# KEYBOARD.net
KiCad netlist of a schematic drawn in Altium Designer
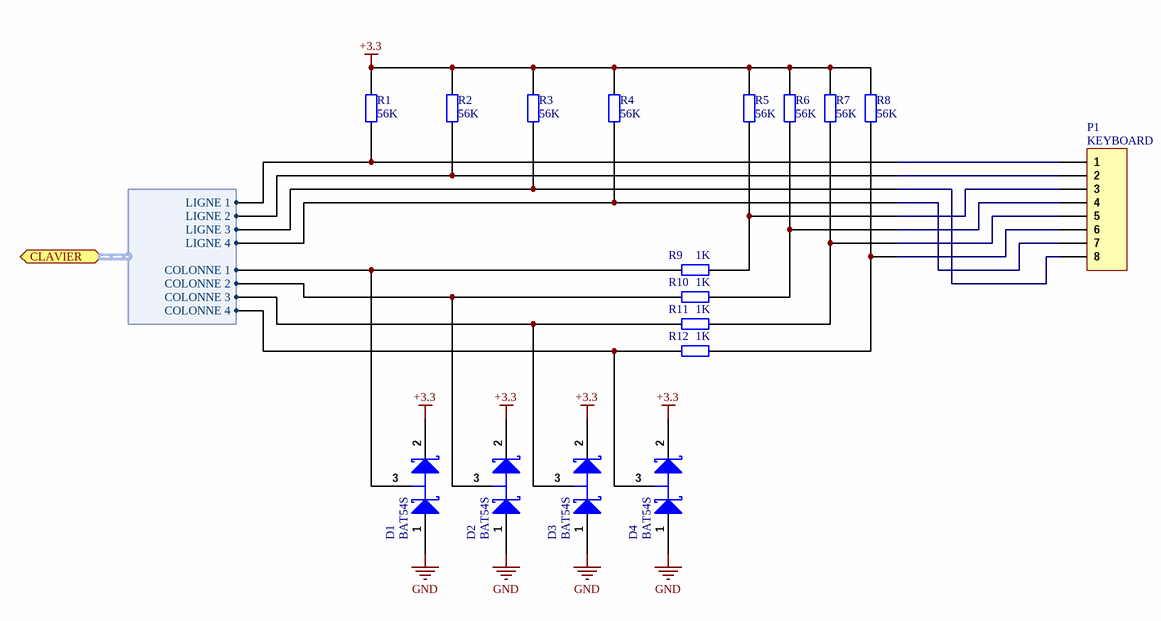
[diagram p0: KEYBOARD.SchDoc]

(export (version "E")
  (design (tool "Eeschema 10.0.6"))
  (components
    (comp (ref "D1")
      (value "BAT54S")
      (footprint "SOT-23")
      (description "Schottky Barrier Double Diode")
      (fields (field (name "MANUFACTURER") "MULTICOMP") (field (name "PUBLISHER") "Altium Limited"))
      (libsource (lib "Philips Discrete Diode - Schottky") (part "BAT54S"))
    )
    (comp (ref "D2")
      (value "BAT54S")
      (footprint "SOT-23")
      (description "Schottky Barrier Double Diode")
      (fields (field (name "MANUFACTURER") "MULTICOMP") (field (name "PUBLISHER") "Altium Limited"))
      (libsource (lib "Philips Discrete Diode - Schottky") (part "BAT54S"))
    )
    (comp (ref "D3")
      (value "BAT54S")
      (footprint "SOT-23")
      (description "Schottky Barrier Double Diode")
      (fields (field (name "MANUFACTURER") "MULTICOMP") (field (name "PUBLISHER") "Altium Limited"))
      (libsource (lib "Philips Discrete Diode - Schottky") (part "BAT54S"))
    )
    (comp (ref "D4")
      (value "BAT54S")
      (footprint "SOT-23")
      (description "Schottky Barrier Double Diode")
      (fields (field (name "MANUFACTURER") "MULTICOMP") (field (name "PUBLISHER") "Altium Limited"))
      (libsource (lib "Philips Discrete Diode - Schottky") (part "BAT54S"))
    )
    (comp (ref "P1")
      (value "KEYBOARD")
      (footprint "M20_1X8")
      (description "Header, 8-Pin")
      (fields
        (field (name "MANUFACTURER") "HARWIN")
        (field (name "MANUFACTURER PART NUMBER") "M20-8770842")
        (field (name "PUBLISHER") "Altium Limited")
      )
      (libsource (lib "Miscellaneous Connectors") (part "Header 8"))
    )
    (comp (ref "R1")
      (value "56K")
      (footprint "R0805")
      (description "Resistor")
      (fields
        (field (name "MANUFACTURER") "MULTICOMP")
        (field (name "MANUFACTURER PART NUMBER") "MC0.1W08051%56KFR")
      )
      (libsource (lib "BRA") (part "Resistor 0805 56K"))
    )
    (comp (ref "R2")
      (value "56K")
      (footprint "R0805")
      (description "Resistor")
      (fields
        (field (name "MANUFACTURER") "MULTICOMP")
        (field (name "MANUFACTURER PART NUMBER") "MC0.1W08051%56KFR")
      )
      (libsource (lib "BRA") (part "Resistor 0805 56K"))
    )
    (comp (ref "R3")
      (value "56K")
      (footprint "R0805")
      (description "Resistor")
      (fields
        (field (name "MANUFACTURER") "MULTICOMP")
        (field (name "MANUFACTURER PART NUMBER") "MC0.1W08051%56KFR")
      )
      (libsource (lib "BRA") (part "Resistor 0805 56K"))
    )
    (comp (ref "R4")
      (value "56K")
      (footprint "R0805")
      (description "Resistor")
      (fields
        (field (name "MANUFACTURER") "MULTICOMP")
        (field (name "MANUFACTURER PART NUMBER") "MC0.1W08051%56KFR")
      )
      (libsource (lib "BRA") (part "Resistor 0805 56K"))
    )
    (comp (ref "R5")
      (value "56K")
      (footprint "R0805")
      (description "Resistor")
      (fields
        (field (name "MANUFACTURER") "MULTICOMP")
        (field (name "MANUFACTURER PART NUMBER") "MC0.1W08051%56KFR")
      )
      (libsource (lib "BRA") (part "Resistor 0805 56K"))
    )
    (comp (ref "R6")
      (value "56K")
      (footprint "R0805")
      (description "Resistor")
      (fields
        (field (name "MANUFACTURER") "MULTICOMP")
        (field (name "MANUFACTURER PART NUMBER") "MC0.1W08051%56KFR")
      )
      (libsource (lib "BRA") (part "Resistor 0805 56K"))
    )
    (comp (ref "R7")
      (value "56K")
      (footprint "R0805")
      (description "Resistor")
      (fields
        (field (name "MANUFACTURER") "MULTICOMP")
        (field (name "MANUFACTURER PART NUMBER") "MC0.1W08051%56KFR")
      )
      (libsource (lib "BRA") (part "Resistor 0805 56K"))
    )
    (comp (ref "R8")
      (value "56K")
      (footprint "R0805")
      (description "Resistor")
      (fields
        (field (name "MANUFACTURER") "MULTICOMP")
        (field (name "MANUFACTURER PART NUMBER") "MC0.1W08051%56KFR")
      )
      (libsource (lib "BRA") (part "Resistor 0805 56K"))
    )
    (comp (ref "R9")
      (value "1K")
      (footprint "R0805")
      (description "Resistor")
      (fields
        (field (name "MANUFACTURER") "MULTICOMP")
        (field (name "MANUFACTURER PART NUMBER") "MC0.1W08051%1KFR")
      )
      (libsource (lib "Miscellaneous Devices") (part "Res2"))
    )
    (comp (ref "R10")
      (value "1K")
      (footprint "R0805")
      (description "Resistor")
      (fields
        (field (name "MANUFACTURER") "MULTICOMP")
        (field (name "MANUFACTURER PART NUMBER") "MC0.1W08051%1KFR")
      )
      (libsource (lib "Miscellaneous Devices") (part "Res2"))
    )
    (comp (ref "R11")
      (value "1K")
      (footprint "R0805")
      (description "Resistor")
      (fields
        (field (name "MANUFACTURER") "MULTICOMP")
        (field (name "MANUFACTURER PART NUMBER") "MC0.1W08051%1KFR")
      )
      (libsource (lib "Miscellaneous Devices") (part "Res2"))
    )
    (comp (ref "R12")
      (value "1K")
      (footprint "R0805")
      (description "Resistor")
      (fields
        (field (name "MANUFACTURER") "MULTICOMP")
        (field (name "MANUFACTURER PART NUMBER") "MC0.1W08051%1KFR")
      )
      (libsource (lib "Miscellaneous Devices") (part "Res2"))
    )
  )
  (nets
    (net (code "2") (name "+3.3") (class "Default")
      (node (ref "D1") (pin "2") (pinfunction "K_2") (pintype "passive"))
      (node (ref "D2") (pin "2") (pinfunction "K_2") (pintype "passive"))
      (node (ref "D3") (pin "2") (pinfunction "K_2") (pintype "passive"))
      (node (ref "D4") (pin "2") (pinfunction "K_2") (pintype "passive"))
      (node (ref "R1") (pin "1") (pinfunction "1_1") (pintype "passive"))
      (node (ref "R2") (pin "1") (pinfunction "1_1") (pintype "passive"))
      (node (ref "R3") (pin "1") (pinfunction "1_1") (pintype "passive"))
      (node (ref "R4") (pin "1") (pinfunction "1_1") (pintype "passive"))
      (node (ref "R5") (pin "1") (pinfunction "1_1") (pintype "passive"))
      (node (ref "R6") (pin "1") (pinfunction "1_1") (pintype "passive"))
      (node (ref "R7") (pin "1") (pinfunction "1_1") (pintype "passive"))
      (node (ref "R8") (pin "1") (pinfunction "1_1") (pintype "passive"))
    )
    (net (code "4") (name "GND") (class "Default")
      (node (ref "D1") (pin "1") (pinfunction "A_1") (pintype "passive"))
      (node (ref "D2") (pin "1") (pinfunction "A_1") (pintype "passive"))
      (node (ref "D3") (pin "1") (pinfunction "A_1") (pintype "passive"))
      (node (ref "D4") (pin "1") (pinfunction "A_1") (pintype "passive"))
    )
    (net (code "5") (name "Net-(D1-C)") (class "Default")
      (node (ref "D1") (pin "3") (pinfunction "C_3") (pintype "passive"))
      (node (ref "R9") (pin "1") (pinfunction "1_1") (pintype "passive"))
    )
    (net (code "6") (name "Net-(D2-C)") (class "Default")
      (node (ref "D2") (pin "3") (pinfunction "C_3") (pintype "passive"))
      (node (ref "R10") (pin "1") (pinfunction "1_1") (pintype "passive"))
    )
    (net (code "7") (name "Net-(D3-C)") (class "Default")
      (node (ref "D3") (pin "3") (pinfunction "C_3") (pintype "passive"))
      (node (ref "R11") (pin "1") (pinfunction "1_1") (pintype "passive"))
    )
    (net (code "8") (name "Net-(D4-C)") (class "Default")
      (node (ref "D4") (pin "3") (pinfunction "C_3") (pintype "passive"))
      (node (ref "R12") (pin "1") (pinfunction "1_1") (pintype "passive"))
    )
    (net (code "9") (name "Net-(P1-Pad1)") (class "Default")
      (node (ref "P1") (pin "1") (pinfunction "1_1") (pintype "passive"))
      (node (ref "R1") (pin "2") (pinfunction "2_2") (pintype "passive"))
    )
    (net (code "10") (name "Net-(P1-Pad2)") (class "Default")
      (node (ref "P1") (pin "2") (pinfunction "2_2") (pintype "passive"))
      (node (ref "R2") (pin "2") (pinfunction "2_2") (pintype "passive"))
    )
    (net (code "11") (name "Net-(P1-Pad3)") (class "Default")
      (node (ref "P1") (pin "3") (pinfunction "3_3") (pintype "passive"))
      (node (ref "R5") (pin "2") (pinfunction "2_2") (pintype "passive"))
      (node (ref "R9") (pin "2") (pinfunction "2_2") (pintype "passive"))
    )
    (net (code "12") (name "Net-(P1-Pad4)") (class "Default")
      (node (ref "P1") (pin "4") (pinfunction "4_4") (pintype "passive"))
      (node (ref "R10") (pin "2") (pinfunction "2_2") (pintype "passive"))
      (node (ref "R6") (pin "2") (pinfunction "2_2") (pintype "passive"))
    )
    (net (code "13") (name "Net-(P1-Pad5)") (class "Default")
      (node (ref "P1") (pin "5") (pinfunction "5_5") (pintype "passive"))
      (node (ref "R11") (pin "2") (pinfunction "2_2") (pintype "passive"))
      (node (ref "R7") (pin "2") (pinfunction "2_2") (pintype "passive"))
    )
    (net (code "14") (name "Net-(P1-Pad6)") (class "Default")
      (node (ref "P1") (pin "6") (pinfunction "6_6") (pintype "passive"))
      (node (ref "R12") (pin "2") (pinfunction "2_2") (pintype "passive"))
      (node (ref "R8") (pin "2") (pinfunction "2_2") (pintype "passive"))
    )
    (net (code "15") (name "Net-(P1-Pad7)") (class "Default")
      (node (ref "P1") (pin "7") (pinfunction "7_7") (pintype "passive"))
      (node (ref "R4") (pin "2") (pinfunction "2_2") (pintype "passive"))
    )
    (net (code "16") (name "Net-(P1-Pad8)") (class "Default")
      (node (ref "P1") (pin "8") (pinfunction "8_8") (pintype "passive"))
      (node (ref "R3") (pin "2") (pinfunction "2_2") (pintype "passive"))
    )
  )
)
